# femtoduinoUSB.net
KiCad netlist of a schematic drawn in EAGLE
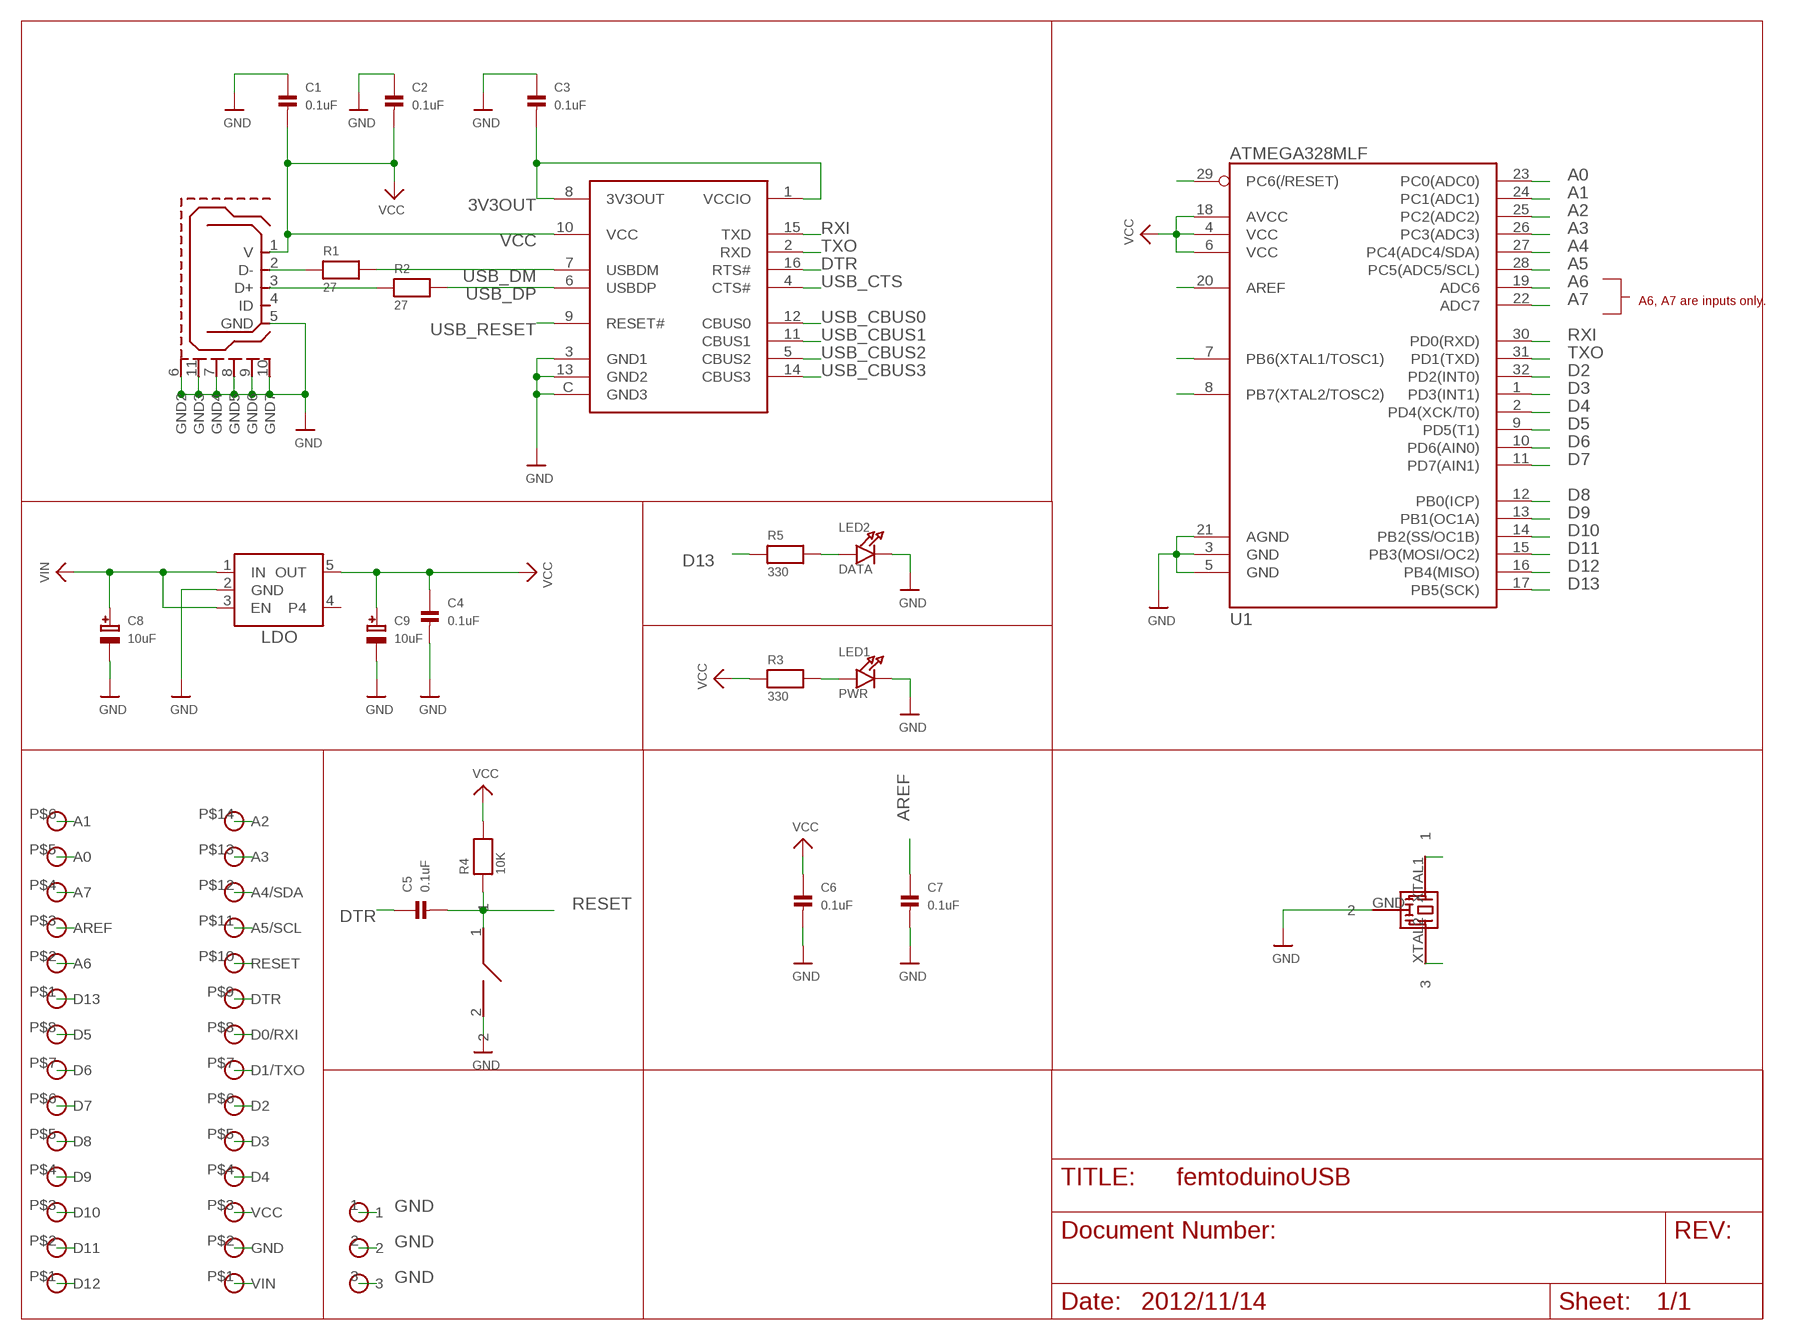
[diagram p0: schematic, sheet 1]

(export (version "E")
  (design (tool "Eeschema 10.0.6"))
  (components
    (comp (ref "C1")
      (value "0.1uF")
      (footprint "eagle-import:_0402MP")
      (libsource (lib "eagle-import") (part "CAP_CERAMIC_0402MP"))
    )
    (comp (ref "C2")
      (value "0.1uF")
      (footprint "eagle-import:_0402MP")
      (libsource (lib "eagle-import") (part "CAP_CERAMIC_0402MP"))
    )
    (comp (ref "C3")
      (value "0.1uF")
      (footprint "eagle-import:_0402MP")
      (libsource (lib "eagle-import") (part "CAP_CERAMIC_0402MP"))
    )
    (comp (ref "C4")
      (value "0.1uF")
      (footprint "eagle-import:_0402MP")
      (libsource (lib "eagle-import") (part "CAP_CERAMIC_0402MP"))
    )
    (comp (ref "C5")
      (value "0.1uF")
      (footprint "eagle-import:_0402MP")
      (libsource (lib "eagle-import") (part "CAP_CERAMIC_0402MP"))
    )
    (comp (ref "C6")
      (value "0.1uF")
      (footprint "eagle-import:_0402MP")
      (libsource (lib "eagle-import") (part "CAP_CERAMIC_0402MP"))
    )
    (comp (ref "C7")
      (value "0.1uF")
      (footprint "eagle-import:_0402MP")
      (libsource (lib "eagle-import") (part "CAP_CERAMIC_0402MP"))
    )
    (comp (ref "C8")
      (value "10uF")
      (footprint "eagle-import:EIA3216-18_A-R")
      (libsource (lib "eagle-import") (part "CAP_TANTALUMA/3216_REFLOW"))
    )
    (comp (ref "C9")
      (value "10uF")
      (footprint "eagle-import:EIA3216-18_A-R")
      (libsource (lib "eagle-import") (part "CAP_TANTALUMA/3216_REFLOW"))
    )
    (comp (ref "LED1")
      (value "PWR")
      (footprint "eagle-import:CHIPLED_0603_NOOUTLINE")
      (libsource (lib "eagle-import") (part "LED0603_NOOUTLINE"))
    )
    (comp (ref "LED2")
      (value "DATA")
      (footprint "eagle-import:CHIPLED_0603_NOOUTLINE")
      (libsource (lib "eagle-import") (part "LED0603_NOOUTLINE"))
    )
    (comp (ref "R1")
      (value "27")
      (footprint "eagle-import:_0402MP")
      (libsource (lib "eagle-import") (part "RESISTOR_0402MP"))
    )
    (comp (ref "R2")
      (value "27")
      (footprint "eagle-import:_0402MP")
      (libsource (lib "eagle-import") (part "RESISTOR_0402MP"))
    )
    (comp (ref "R3")
      (value "330")
      (footprint "eagle-import:_0402MP")
      (libsource (lib "eagle-import") (part "RESISTOR_0402MP"))
    )
    (comp (ref "R4")
      (value "10K")
      (footprint "eagle-import:_0402")
      (libsource (lib "eagle-import") (part "RESISTOR_0402"))
    )
    (comp (ref "R5")
      (value "330")
      (footprint "eagle-import:_0402MP")
      (libsource (lib "eagle-import") (part "RESISTOR_0402MP"))
    )
    (comp (ref "U$1")
      (value "FT230XQ")
      (footprint "eagle-import:FT230XQ")
      (libsource (lib "eagle-import") (part "FT230XQ"))
    )
    (comp (ref "U$2")
      (value "05_PINHEAD_1X6")
      (footprint "eagle-import:05_PINHEAD_1X6_PACKAGE")
      (libsource (lib "eagle-import") (part "05_PINHEAD_1X6"))
    )
    (comp (ref "U$3")
      (value "05_PINHEAD_1X8")
      (footprint "eagle-import:05_PINHEAD_1X8_PACKAGE")
      (libsource (lib "eagle-import") (part "05_PINHEAD_1X8"))
    )
    (comp (ref "U$4")
      (value "05_PINHEAD_1X14")
      (footprint "eagle-import:05_PINHEAD_1X14_PACKAGE")
      (libsource (lib "eagle-import") (part "05_PINHEAD_1X14"))
    )
    (comp (ref "U$6")
      (value "USB_MICROB")
      (footprint "eagle-import:USB_MICROB_PACKAGE")
      (libsource (lib "eagle-import") (part "USB_MICROB"))
    )
    (comp (ref "U$10")
      (value "LDO_REGULATOR")
      (footprint "eagle-import:LDO_REGULATOR")
      (libsource (lib "eagle-import") (part "LDO_REGULATOR"))
    )
    (comp (ref "U$17")
      (value "SPST_SMD")
      (footprint "eagle-import:SPST_SMD")
      (libsource (lib "eagle-import") (part "SPST_SMD"))
    )
    (comp (ref "U$22")
      (value "CSTCE16MOV51-RO")
      (footprint "eagle-import:CSTCE16M0V51-RO_PACKAGE")
      (libsource (lib "eagle-import") (part "CSTCE16MOV51-RO"))
    )
    (comp (ref "U$28")
      (value "05_PINHEAD_HEADER_1X3")
      (footprint "eagle-import:05_PINHEAD_1X3_HEAD_PACKAGE")
      (libsource (lib "eagle-import") (part "05_PINHEAD_HEADER_1X3"))
    )
    (comp (ref "U1")
      (value "ATMEGA328MLF")
      (footprint "eagle-import:MLF32")
      (libsource (lib "eagle-import") (part "ATMEGA168MLF"))
    )
  )
  (nets
    (net (code "1") (name "/3V3OUT") (class "Default")
      (node (ref "C3") (pin "2") (pinfunction "P$2_2") (pintype "passive"))
      (node (ref "U$1") (pin "1") (pinfunction "VCCIO_1") (pintype "bidirectional"))
      (node (ref "U$1") (pin "8") (pinfunction "3V3OUT_8") (pintype "bidirectional"))
    )
    (net (code "2") (name "/A0") (class "Default")
      (node (ref "U$2") (pin "P$5") (pinfunction "A0_P$5") (pintype "bidirectional"))
      (node (ref "U1") (pin "23") (pinfunction "PC0(ADC0)_23") (pintype "bidirectional"))
    )
    (net (code "3") (name "/A1") (class "Default")
      (node (ref "U$2") (pin "P$6") (pinfunction "A1_P$6") (pintype "bidirectional"))
      (node (ref "U1") (pin "24") (pinfunction "PC1(ADC1)_24") (pintype "bidirectional"))
    )
    (net (code "4") (name "/A2") (class "Default")
      (node (ref "U$4") (pin "P$14") (pinfunction "A2_P$14") (pintype "bidirectional"))
      (node (ref "U1") (pin "25") (pinfunction "PC2(ADC2)_25") (pintype "bidirectional"))
    )
    (net (code "5") (name "/A3") (class "Default")
      (node (ref "U$4") (pin "P$13") (pinfunction "A3_P$13") (pintype "bidirectional"))
      (node (ref "U1") (pin "26") (pinfunction "PC3(ADC3)_26") (pintype "bidirectional"))
    )
    (net (code "6") (name "/A4") (class "Default")
      (node (ref "U$4") (pin "P$12") (pinfunction "A4/SDA_P$12") (pintype "bidirectional"))
      (node (ref "U1") (pin "27") (pinfunction "PC4(ADC4/SDA)_27") (pintype "bidirectional"))
    )
    (net (code "7") (name "/A5") (class "Default")
      (node (ref "U$4") (pin "P$11") (pinfunction "A5/SCL_P$11") (pintype "bidirectional"))
      (node (ref "U1") (pin "28") (pinfunction "PC5(ADC5/SCL)_28") (pintype "bidirectional"))
    )
    (net (code "8") (name "/A6") (class "Default")
      (node (ref "U$2") (pin "P$2") (pinfunction "A6_P$2") (pintype "bidirectional"))
      (node (ref "U1") (pin "19") (pinfunction "ADC6_19") (pintype "bidirectional"))
    )
    (net (code "9") (name "/A7") (class "Default")
      (node (ref "U$2") (pin "P$4") (pinfunction "A7_P$4") (pintype "bidirectional"))
      (node (ref "U1") (pin "22") (pinfunction "ADC7_22") (pintype "bidirectional"))
    )
    (net (code "10") (name "/AREF") (class "Default")
      (node (ref "C7") (pin "1") (pinfunction "P$1_1") (pintype "passive"))
      (node (ref "U$2") (pin "P$3") (pinfunction "AREF_P$3") (pintype "bidirectional"))
      (node (ref "U1") (pin "20") (pinfunction "AREF_20") (pintype "bidirectional"))
    )
    (net (code "11") (name "/D2") (class "Default")
      (node (ref "U$4") (pin "P$6") (pinfunction "D2_P$6") (pintype "bidirectional"))
      (node (ref "U1") (pin "32") (pinfunction "PD2(INT0)_32") (pintype "bidirectional"))
    )
    (net (code "12") (name "/D3") (class "Default")
      (node (ref "U$4") (pin "P$5") (pinfunction "D3_P$5") (pintype "bidirectional"))
      (node (ref "U1") (pin "1") (pinfunction "PD3(INT1)_1") (pintype "bidirectional"))
    )
    (net (code "13") (name "/D4") (class "Default")
      (node (ref "U$4") (pin "P$4") (pinfunction "D4_P$4") (pintype "bidirectional"))
      (node (ref "U1") (pin "2") (pinfunction "PD4(XCK/T0)_2") (pintype "bidirectional"))
    )
    (net (code "14") (name "/D5") (class "Default")
      (node (ref "U$3") (pin "P$8") (pinfunction "D5_P$8") (pintype "bidirectional"))
      (node (ref "U1") (pin "9") (pinfunction "PD5(T1)_9") (pintype "bidirectional"))
    )
    (net (code "15") (name "/D6") (class "Default")
      (node (ref "U$3") (pin "P$7") (pinfunction "D6_P$7") (pintype "bidirectional"))
      (node (ref "U1") (pin "10") (pinfunction "PD6(AIN0)_10") (pintype "bidirectional"))
    )
    (net (code "16") (name "/D7") (class "Default")
      (node (ref "U$3") (pin "P$6") (pinfunction "D7_P$6") (pintype "bidirectional"))
      (node (ref "U1") (pin "11") (pinfunction "PD7(AIN1)_11") (pintype "bidirectional"))
    )
    (net (code "17") (name "/D8") (class "Default")
      (node (ref "U$3") (pin "P$5") (pinfunction "D8_P$5") (pintype "bidirectional"))
      (node (ref "U1") (pin "12") (pinfunction "PB0(ICP)_12") (pintype "bidirectional"))
    )
    (net (code "18") (name "/D9") (class "Default")
      (node (ref "U$3") (pin "P$4") (pinfunction "D9_P$4") (pintype "bidirectional"))
      (node (ref "U1") (pin "13") (pinfunction "PB1(OC1A)_13") (pintype "bidirectional"))
    )
    (net (code "19") (name "/D10") (class "Default")
      (node (ref "U$3") (pin "P$3") (pinfunction "D10_P$3") (pintype "bidirectional"))
      (node (ref "U1") (pin "14") (pinfunction "PB2(SS/OC1B)_14") (pintype "bidirectional"))
    )
    (net (code "20") (name "/D11") (class "Default")
      (node (ref "U$3") (pin "P$2") (pinfunction "D11_P$2") (pintype "bidirectional"))
      (node (ref "U1") (pin "15") (pinfunction "PB3(MOSI/OC2)_15") (pintype "bidirectional"))
    )
    (net (code "21") (name "/D12") (class "Default")
      (node (ref "U$3") (pin "P$1") (pinfunction "D12_P$1") (pintype "bidirectional"))
      (node (ref "U1") (pin "16") (pinfunction "PB4(MISO)_16") (pintype "bidirectional"))
    )
    (net (code "22") (name "/D13") (class "Default")
      (node (ref "R5") (pin "1") (pinfunction "1_1") (pintype "passive"))
      (node (ref "U$2") (pin "P$1") (pinfunction "D13_P$1") (pintype "bidirectional"))
      (node (ref "U1") (pin "17") (pinfunction "PB5(SCK)_17") (pintype "bidirectional"))
    )
    (net (code "23") (name "/DTR") (class "Default")
      (node (ref "C5") (pin "1") (pinfunction "P$1_1") (pintype "passive"))
      (node (ref "U$1") (pin "16") (pinfunction "RTS#_16") (pintype "bidirectional"))
      (node (ref "U$4") (pin "P$9") (pinfunction "DTR_P$9") (pintype "bidirectional"))
    )
    (net (code "24") (name "/RESET") (class "Default")
      (node (ref "C5") (pin "2") (pinfunction "P$2_2") (pintype "passive"))
      (node (ref "R4") (pin "1") (pinfunction "1_1") (pintype "passive"))
      (node (ref "U$17") (pin "1") (pinfunction "1_1") (pintype "bidirectional"))
      (node (ref "U$4") (pin "P$10") (pinfunction "RESET_P$10") (pintype "bidirectional"))
      (node (ref "U1") (pin "29") (pinfunction "PC6(/RESET)_29") (pintype "bidirectional"))
    )
    (net (code "25") (name "/RXI") (class "Default")
      (node (ref "U$1") (pin "15") (pinfunction "TXD_15") (pintype "bidirectional"))
      (node (ref "U$4") (pin "P$8") (pinfunction "D0/RXI_P$8") (pintype "bidirectional"))
      (node (ref "U1") (pin "30") (pinfunction "PD0(RXD)_30") (pintype "bidirectional"))
    )
    (net (code "26") (name "/TXO") (class "Default")
      (node (ref "U$1") (pin "2") (pinfunction "RXD_2") (pintype "bidirectional"))
      (node (ref "U$4") (pin "P$7") (pinfunction "D1/TXO_P$7") (pintype "bidirectional"))
      (node (ref "U1") (pin "31") (pinfunction "PD1(TXD)_31") (pintype "bidirectional"))
    )
    (net (code "27") (name "/USB_CBUS0") (class "Default")
      (node (ref "U$1") (pin "12") (pinfunction "CBUS0_12") (pintype "bidirectional"))
    )
    (net (code "28") (name "/USB_CBUS1") (class "Default")
      (node (ref "U$1") (pin "11") (pinfunction "CBUS1_11") (pintype "bidirectional"))
    )
    (net (code "29") (name "/USB_CBUS2") (class "Default")
      (node (ref "U$1") (pin "5") (pinfunction "CBUS2_5") (pintype "bidirectional"))
    )
    (net (code "30") (name "/USB_CBUS3") (class "Default")
      (node (ref "U$1") (pin "14") (pinfunction "CBUS3_14") (pintype "bidirectional"))
    )
    (net (code "31") (name "/USB_CTS") (class "Default")
      (node (ref "U$1") (pin "4") (pinfunction "CTS#_4") (pintype "bidirectional"))
    )
    (net (code "32") (name "/USB_DM") (class "Default")
      (node (ref "R1") (pin "2") (pinfunction "2_2") (pintype "passive"))
      (node (ref "U$1") (pin "7") (pinfunction "USBDM_7") (pintype "bidirectional"))
    )
    (net (code "33") (name "/USB_DP") (class "Default")
      (node (ref "R2") (pin "2") (pinfunction "2_2") (pintype "passive"))
      (node (ref "U$1") (pin "6") (pinfunction "USBDP_6") (pintype "bidirectional"))
    )
    (net (code "34") (name "/USB_RESET") (class "Default")
      (node (ref "U$1") (pin "9") (pinfunction "RESET#_9") (pintype "bidirectional"))
    )
    (net (code "35") (name "/XTAL1") (class "Default")
      (node (ref "U$22") (pin "XTAL1") (pinfunction "1_XTAL1") (pintype "bidirectional"))
      (node (ref "U1") (pin "7") (pinfunction "PB6(XTAL1/TOSC1)_7") (pintype "bidirectional"))
    )
    (net (code "36") (name "/XTAL2") (class "Default")
      (node (ref "U$22") (pin "XTAL2") (pinfunction "3_XTAL2") (pintype "bidirectional"))
      (node (ref "U1") (pin "8") (pinfunction "PB7(XTAL2/TOSC2)_8") (pintype "bidirectional"))
    )
    (net (code "37") (name "GND") (class "Default")
      (node (ref "C1") (pin "1") (pinfunction "P$1_1") (pintype "passive"))
      (node (ref "C2") (pin "1") (pinfunction "P$1_1") (pintype "passive"))
      (node (ref "C3") (pin "1") (pinfunction "P$1_1") (pintype "passive"))
      (node (ref "C4") (pin "2") (pinfunction "P$2_2") (pintype "passive"))
      (node (ref "C6") (pin "2") (pinfunction "P$2_2") (pintype "passive"))
      (node (ref "C7") (pin "2") (pinfunction "P$2_2") (pintype "passive"))
      (node (ref "C8") (pin "-") (pinfunction "-_-") (pintype "passive"))
      (node (ref "C9") (pin "-") (pinfunction "-_-") (pintype "passive"))
      (node (ref "LED1") (pin "C") (pinfunction "C_C") (pintype "passive"))
      (node (ref "LED2") (pin "C") (pinfunction "C_C") (pintype "passive"))
      (node (ref "U$1") (pin "13") (pinfunction "GND2_13") (pintype "bidirectional"))
      (node (ref "U$1") (pin "3") (pinfunction "GND1_3") (pintype "bidirectional"))
      (node (ref "U$1") (pin "C") (pinfunction "GND3_C") (pintype "bidirectional"))
      (node (ref "U$10") (pin "2") (pinfunction "GND_2") (pintype "bidirectional"))
      (node (ref "U$17") (pin "2") (pinfunction "2_2") (pintype "bidirectional"))
      (node (ref "U$22") (pin "GND") (pinfunction "2_GND") (pintype "bidirectional"))
      (node (ref "U$28") (pin "1") (pinfunction "1_1") (pintype "bidirectional"))
      (node (ref "U$28") (pin "2") (pinfunction "2_2") (pintype "bidirectional"))
      (node (ref "U$28") (pin "3") (pinfunction "3_3") (pintype "bidirectional"))
      (node (ref "U$4") (pin "P$2") (pinfunction "GND_P$2") (pintype "bidirectional"))
      (node (ref "U$6") (pin "10") (pinfunction "GND7_10") (pintype "bidirectional"))
      (node (ref "U$6") (pin "11") (pinfunction "GND3_11") (pintype "bidirectional"))
      (node (ref "U$6") (pin "5") (pinfunction "GND_5") (pintype "bidirectional"))
      (node (ref "U$6") (pin "6") (pinfunction "GND2_6") (pintype "bidirectional"))
      (node (ref "U$6") (pin "7") (pinfunction "GND4_7") (pintype "bidirectional"))
      (node (ref "U$6") (pin "8") (pinfunction "GND5_8") (pintype "bidirectional"))
      (node (ref "U$6") (pin "9") (pinfunction "GND6_9") (pintype "bidirectional"))
      (node (ref "U1") (pin "21") (pinfunction "AGND_21") (pintype "bidirectional"))
      (node (ref "U1") (pin "3") (pinfunction "GND_3") (pintype "bidirectional"))
      (node (ref "U1") (pin "5") (pinfunction "GND_5") (pintype "bidirectional"))
    )
    (net (code "38") (name "Net-(LED1-PadA)") (class "Default")
      (node (ref "LED1") (pin "A") (pinfunction "A_A") (pintype "passive"))
      (node (ref "R3") (pin "2") (pinfunction "2_2") (pintype "passive"))
    )
    (net (code "39") (name "Net-(LED2-PadA)") (class "Default")
      (node (ref "LED2") (pin "A") (pinfunction "A_A") (pintype "passive"))
      (node (ref "R5") (pin "2") (pinfunction "2_2") (pintype "passive"))
    )
    (net (code "40") (name "Net-(U$6-D+)") (class "Default")
      (node (ref "R2") (pin "1") (pinfunction "1_1") (pintype "passive"))
      (node (ref "U$6") (pin "3") (pinfunction "D+_3") (pintype "bidirectional"))
    )
    (net (code "41") (name "Net-(U$6-D-)") (class "Default")
      (node (ref "R1") (pin "1") (pinfunction "1_1") (pintype "passive"))
      (node (ref "U$6") (pin "2") (pinfunction "D-_2") (pintype "bidirectional"))
    )
    (net (code "42") (name "VCC") (class "Default")
      (node (ref "C1") (pin "2") (pinfunction "P$2_2") (pintype "passive"))
      (node (ref "C2") (pin "2") (pinfunction "P$2_2") (pintype "passive"))
      (node (ref "C4") (pin "1") (pinfunction "P$1_1") (pintype "passive"))
      (node (ref "C6") (pin "1") (pinfunction "P$1_1") (pintype "passive"))
      (node (ref "C9") (pin "+") (pinfunction "+_+") (pintype "passive"))
      (node (ref "R3") (pin "1") (pinfunction "1_1") (pintype "passive"))
      (node (ref "R4") (pin "2") (pinfunction "2_2") (pintype "passive"))
      (node (ref "U$1") (pin "10") (pinfunction "VCC_10") (pintype "bidirectional"))
      (node (ref "U$10") (pin "5") (pinfunction "OUT_5") (pintype "bidirectional"))
      (node (ref "U$4") (pin "P$3") (pinfunction "VCC_P$3") (pintype "bidirectional"))
      (node (ref "U$6") (pin "1") (pinfunction "V_1") (pintype "bidirectional"))
      (node (ref "U1") (pin "18") (pinfunction "AVCC_18") (pintype "bidirectional"))
      (node (ref "U1") (pin "4") (pinfunction "VCC_4") (pintype "bidirectional"))
      (node (ref "U1") (pin "6") (pinfunction "VCC_6") (pintype "bidirectional"))
    )
    (net (code "43") (name "VIN") (class "Default")
      (node (ref "C8") (pin "+") (pinfunction "+_+") (pintype "passive"))
      (node (ref "U$10") (pin "1") (pinfunction "IN_1") (pintype "bidirectional"))
      (node (ref "U$10") (pin "3") (pinfunction "EN_3") (pintype "bidirectional"))
      (node (ref "U$4") (pin "P$1") (pinfunction "VIN_P$1") (pintype "bidirectional"))
    )
    (net (code "44") (name "unconnected-(U$6-ID-Pad4)") (class "Default")
      (node (ref "U$6") (pin "4") (pinfunction "ID_4") (pintype "bidirectional"))
    )
    (net (code "45") (name "unconnected-(U$10-P4-Pad4)") (class "Default")
      (node (ref "U$10") (pin "4") (pinfunction "P4_4") (pintype "bidirectional"))
    )
  )
)
